# CMoy-Pro-V_1_0_0_1a.net
KiCad netlist of a schematic drawn in EAGLE
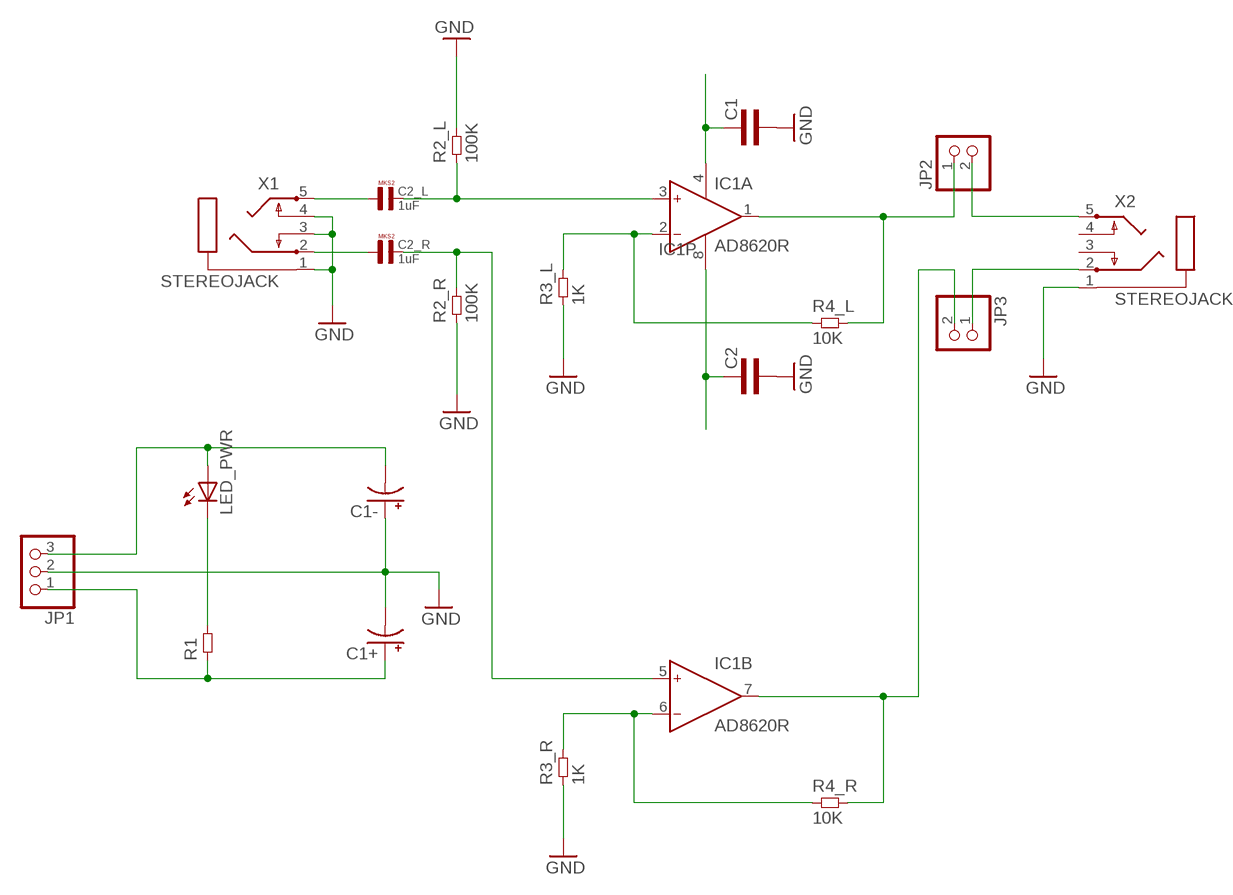
[diagram p0: schematic, sheet 1]

(export (version "E")
  (design (tool "Eeschema 10.0.6"))
  (components
    (comp (ref "C1")
      (value "CAP0603L3")
      (footprint "eagle-import:0603L3")
      (libsource (lib "eagle-import") (part "CAP0603L3"))
    )
    (comp (ref "C1+")
      (value "CPOL-US140CLH-1010")
      (footprint "eagle-import:140CLH-1010")
      (libsource (lib "eagle-import") (part "CPOL-US140CLH-1010"))
    )
    (comp (ref "C1-")
      (value "CPOL-US140CLH-1010")
      (footprint "eagle-import:140CLH-1010")
      (libsource (lib "eagle-import") (part "CPOL-US140CLH-1010"))
    )
    (comp (ref "C2")
      (value "CAP0603L3")
      (footprint "eagle-import:0603L3")
      (libsource (lib "eagle-import") (part "CAP0603L3"))
    )
    (comp (ref "C2_L")
      (value "1uF")
      (footprint "eagle-import:R5B5")
      (libsource (lib "eagle-import") (part "1,0µF"))
    )
    (comp (ref "C2_R")
      (value "1uF")
      (footprint "eagle-import:R5B5")
      (libsource (lib "eagle-import") (part "1,0µF"))
    )
    (comp (ref "IC1")
      (value "AD8620R")
      (footprint "eagle-import:SO8")
      (fields (field (name "MF") "ALTERA CORPORATION") (field (name "MPN") "AD8620ARZ"))
      (libsource (lib "eagle-import") (part "AD8620R"))
    )
    (comp (ref "JP1")
      (value "PINHD-1X3")
      (footprint "eagle-import:1X03")
      (libsource (lib "eagle-import") (part "PINHD-1X3"))
    )
    (comp (ref "JP2")
      (value "PINHD-1X2")
      (footprint "eagle-import:1X02")
      (libsource (lib "eagle-import") (part "PINHD-1X2"))
    )
    (comp (ref "JP3")
      (value "PINHD-1X2")
      (footprint "eagle-import:1X02")
      (libsource (lib "eagle-import") (part "PINHD-1X2"))
    )
    (comp (ref "LED_PWR")
      (value "LEDCHIP-LED0603")
      (footprint "eagle-import:CHIP-LED0603")
      (libsource (lib "eagle-import") (part "LEDCHIP-LED0603"))
    )
    (comp (ref "R1")
      (value "RES0603L3")
      (footprint "eagle-import:0603L3")
      (libsource (lib "eagle-import") (part "RES0603L3"))
    )
    (comp (ref "R2_L")
      (value "100K")
      (footprint "eagle-import:0603L3")
      (libsource (lib "eagle-import") (part "RES0603L3"))
    )
    (comp (ref "R2_R")
      (value "100K")
      (footprint "eagle-import:0603L3")
      (libsource (lib "eagle-import") (part "RES0603L3"))
    )
    (comp (ref "R3_L")
      (value "1K")
      (footprint "eagle-import:0603L3")
      (libsource (lib "eagle-import") (part "RES0603L3"))
    )
    (comp (ref "R3_R")
      (value "1K")
      (footprint "eagle-import:0603L3")
      (libsource (lib "eagle-import") (part "RES0603L3"))
    )
    (comp (ref "R4_L")
      (value "10K")
      (footprint "eagle-import:0603L3")
      (libsource (lib "eagle-import") (part "RES0603L3"))
    )
    (comp (ref "R4_R")
      (value "10K")
      (footprint "eagle-import:0603L3")
      (libsource (lib "eagle-import") (part "RES0603L3"))
    )
    (comp (ref "X1")
      (value "STEREOJACK")
      (footprint "eagle-import:STX3100")
      (libsource (lib "eagle-import") (part "STEREOJACK"))
    )
    (comp (ref "X2")
      (value "STEREOJACK")
      (footprint "eagle-import:STX3100")
      (libsource (lib "eagle-import") (part "STEREOJACK"))
    )
  )
  (nets
    (net (code "1") (name "/V+") (class "Default")
      (node (ref "C1+") (pin "+") (pinfunction "+_+") (pintype "passive"))
      (node (ref "C2") (pin "P$1") (pinfunction "1_P$1") (pintype "bidirectional"))
      (node (ref "IC1") (pin "8") (pinfunction "V+_8") (pintype "power_in"))
      (node (ref "JP1") (pin "1") (pinfunction "1_1") (pintype "passive"))
      (node (ref "R1") (pin "P$1") (pinfunction "1_P$1") (pintype "bidirectional"))
    )
    (net (code "2") (name "/V-") (class "Default")
      (node (ref "C1") (pin "P$1") (pinfunction "1_P$1") (pintype "bidirectional"))
      (node (ref "C1-") (pin "-") (pinfunction "-_-") (pintype "passive"))
      (node (ref "IC1") (pin "4") (pinfunction "V-_4") (pintype "power_in"))
      (node (ref "JP1") (pin "3") (pinfunction "3_3") (pintype "passive"))
      (node (ref "LED_PWR") (pin "A") (pinfunction "A_A") (pintype "passive"))
    )
    (net (code "3") (name "GND") (class "Default")
      (node (ref "C1") (pin "P$2") (pinfunction "2_P$2") (pintype "bidirectional"))
      (node (ref "C1+") (pin "-") (pinfunction "-_-") (pintype "passive"))
      (node (ref "C1-") (pin "+") (pinfunction "+_+") (pintype "passive"))
      (node (ref "C2") (pin "P$2") (pinfunction "2_P$2") (pintype "bidirectional"))
      (node (ref "JP1") (pin "2") (pinfunction "2_2") (pintype "passive"))
      (node (ref "R2_L") (pin "P$2") (pinfunction "2_P$2") (pintype "bidirectional"))
      (node (ref "R2_R") (pin "P$1") (pinfunction "1_P$1") (pintype "bidirectional"))
      (node (ref "R3_L") (pin "P$1") (pinfunction "1_P$1") (pintype "bidirectional"))
      (node (ref "R3_R") (pin "P$1") (pinfunction "1_P$1") (pintype "bidirectional"))
      (node (ref "X1") (pin "1") (pinfunction "1_1") (pintype "passive"))
      (node (ref "X1") (pin "3") (pinfunction "3_3") (pintype "passive"))
      (node (ref "X1") (pin "4") (pinfunction "4_4") (pintype "passive"))
      (node (ref "X2") (pin "1") (pinfunction "1_1") (pintype "passive"))
    )
    (net (code "4") (name "Net-(C2_L-Pad1)") (class "Default")
      (node (ref "C2_L") (pin "1") (pinfunction "1_1") (pintype "passive"))
      (node (ref "X1") (pin "5") (pinfunction "5_5") (pintype "passive"))
    )
    (net (code "5") (name "Net-(C2_R-Pad1)") (class "Default")
      (node (ref "C2_R") (pin "1") (pinfunction "1_1") (pintype "passive"))
      (node (ref "X1") (pin "2") (pinfunction "2_2") (pintype "passive"))
    )
    (net (code "6") (name "Net-(IC1A-IN+)") (class "Default")
      (node (ref "C2_L") (pin "2") (pinfunction "2_2") (pintype "passive"))
      (node (ref "IC1") (pin "3") (pinfunction "IN+_3") (pintype "input"))
      (node (ref "R2_L") (pin "P$1") (pinfunction "1_P$1") (pintype "bidirectional"))
    )
    (net (code "7") (name "Net-(IC1A-IN-)") (class "Default")
      (node (ref "IC1") (pin "2") (pinfunction "IN-_2") (pintype "input"))
      (node (ref "R3_L") (pin "P$2") (pinfunction "2_P$2") (pintype "bidirectional"))
      (node (ref "R4_L") (pin "P$1") (pinfunction "1_P$1") (pintype "bidirectional"))
    )
    (net (code "8") (name "Net-(IC1A-OUT)") (class "Default")
      (node (ref "IC1") (pin "1") (pinfunction "OUT_1") (pintype "output"))
      (node (ref "JP2") (pin "1") (pinfunction "1_1") (pintype "passive"))
      (node (ref "R4_L") (pin "P$2") (pinfunction "2_P$2") (pintype "bidirectional"))
    )
    (net (code "9") (name "Net-(IC1B-IN+)") (class "Default")
      (node (ref "C2_R") (pin "2") (pinfunction "2_2") (pintype "passive"))
      (node (ref "IC1") (pin "5") (pinfunction "IN+_5") (pintype "input"))
      (node (ref "R2_R") (pin "P$2") (pinfunction "2_P$2") (pintype "bidirectional"))
    )
    (net (code "10") (name "Net-(IC1B-IN-)") (class "Default")
      (node (ref "IC1") (pin "6") (pinfunction "IN-_6") (pintype "input"))
      (node (ref "R3_R") (pin "P$2") (pinfunction "2_P$2") (pintype "bidirectional"))
      (node (ref "R4_R") (pin "P$1") (pinfunction "1_P$1") (pintype "bidirectional"))
    )
    (net (code "11") (name "Net-(IC1B-OUT)") (class "Default")
      (node (ref "IC1") (pin "7") (pinfunction "OUT_7") (pintype "output"))
      (node (ref "JP3") (pin "2") (pinfunction "2_2") (pintype "passive"))
      (node (ref "R4_R") (pin "P$2") (pinfunction "2_P$2") (pintype "bidirectional"))
    )
    (net (code "12") (name "Net-(JP2-Pad2)") (class "Default")
      (node (ref "JP2") (pin "2") (pinfunction "2_2") (pintype "passive"))
      (node (ref "X2") (pin "5") (pinfunction "5_5") (pintype "passive"))
    )
    (net (code "13") (name "Net-(JP3-Pad1)") (class "Default")
      (node (ref "JP3") (pin "1") (pinfunction "1_1") (pintype "passive"))
      (node (ref "X2") (pin "2") (pinfunction "2_2") (pintype "passive"))
    )
    (net (code "14") (name "Net-(R1-2)") (class "Default")
      (node (ref "LED_PWR") (pin "C") (pinfunction "C_C") (pintype "passive"))
      (node (ref "R1") (pin "P$2") (pinfunction "2_P$2") (pintype "bidirectional"))
    )
    (net (code "15") (name "unconnected-(X2-Pad3)") (class "Default")
      (node (ref "X2") (pin "3") (pinfunction "3_3") (pintype "passive"))
    )
    (net (code "16") (name "unconnected-(X2-Pad4)") (class "Default")
      (node (ref "X2") (pin "4") (pinfunction "4_4") (pintype "passive"))
    )
  )
)
